# esp8266-adapter.net
KiCad netlist of a schematic drawn in EAGLE
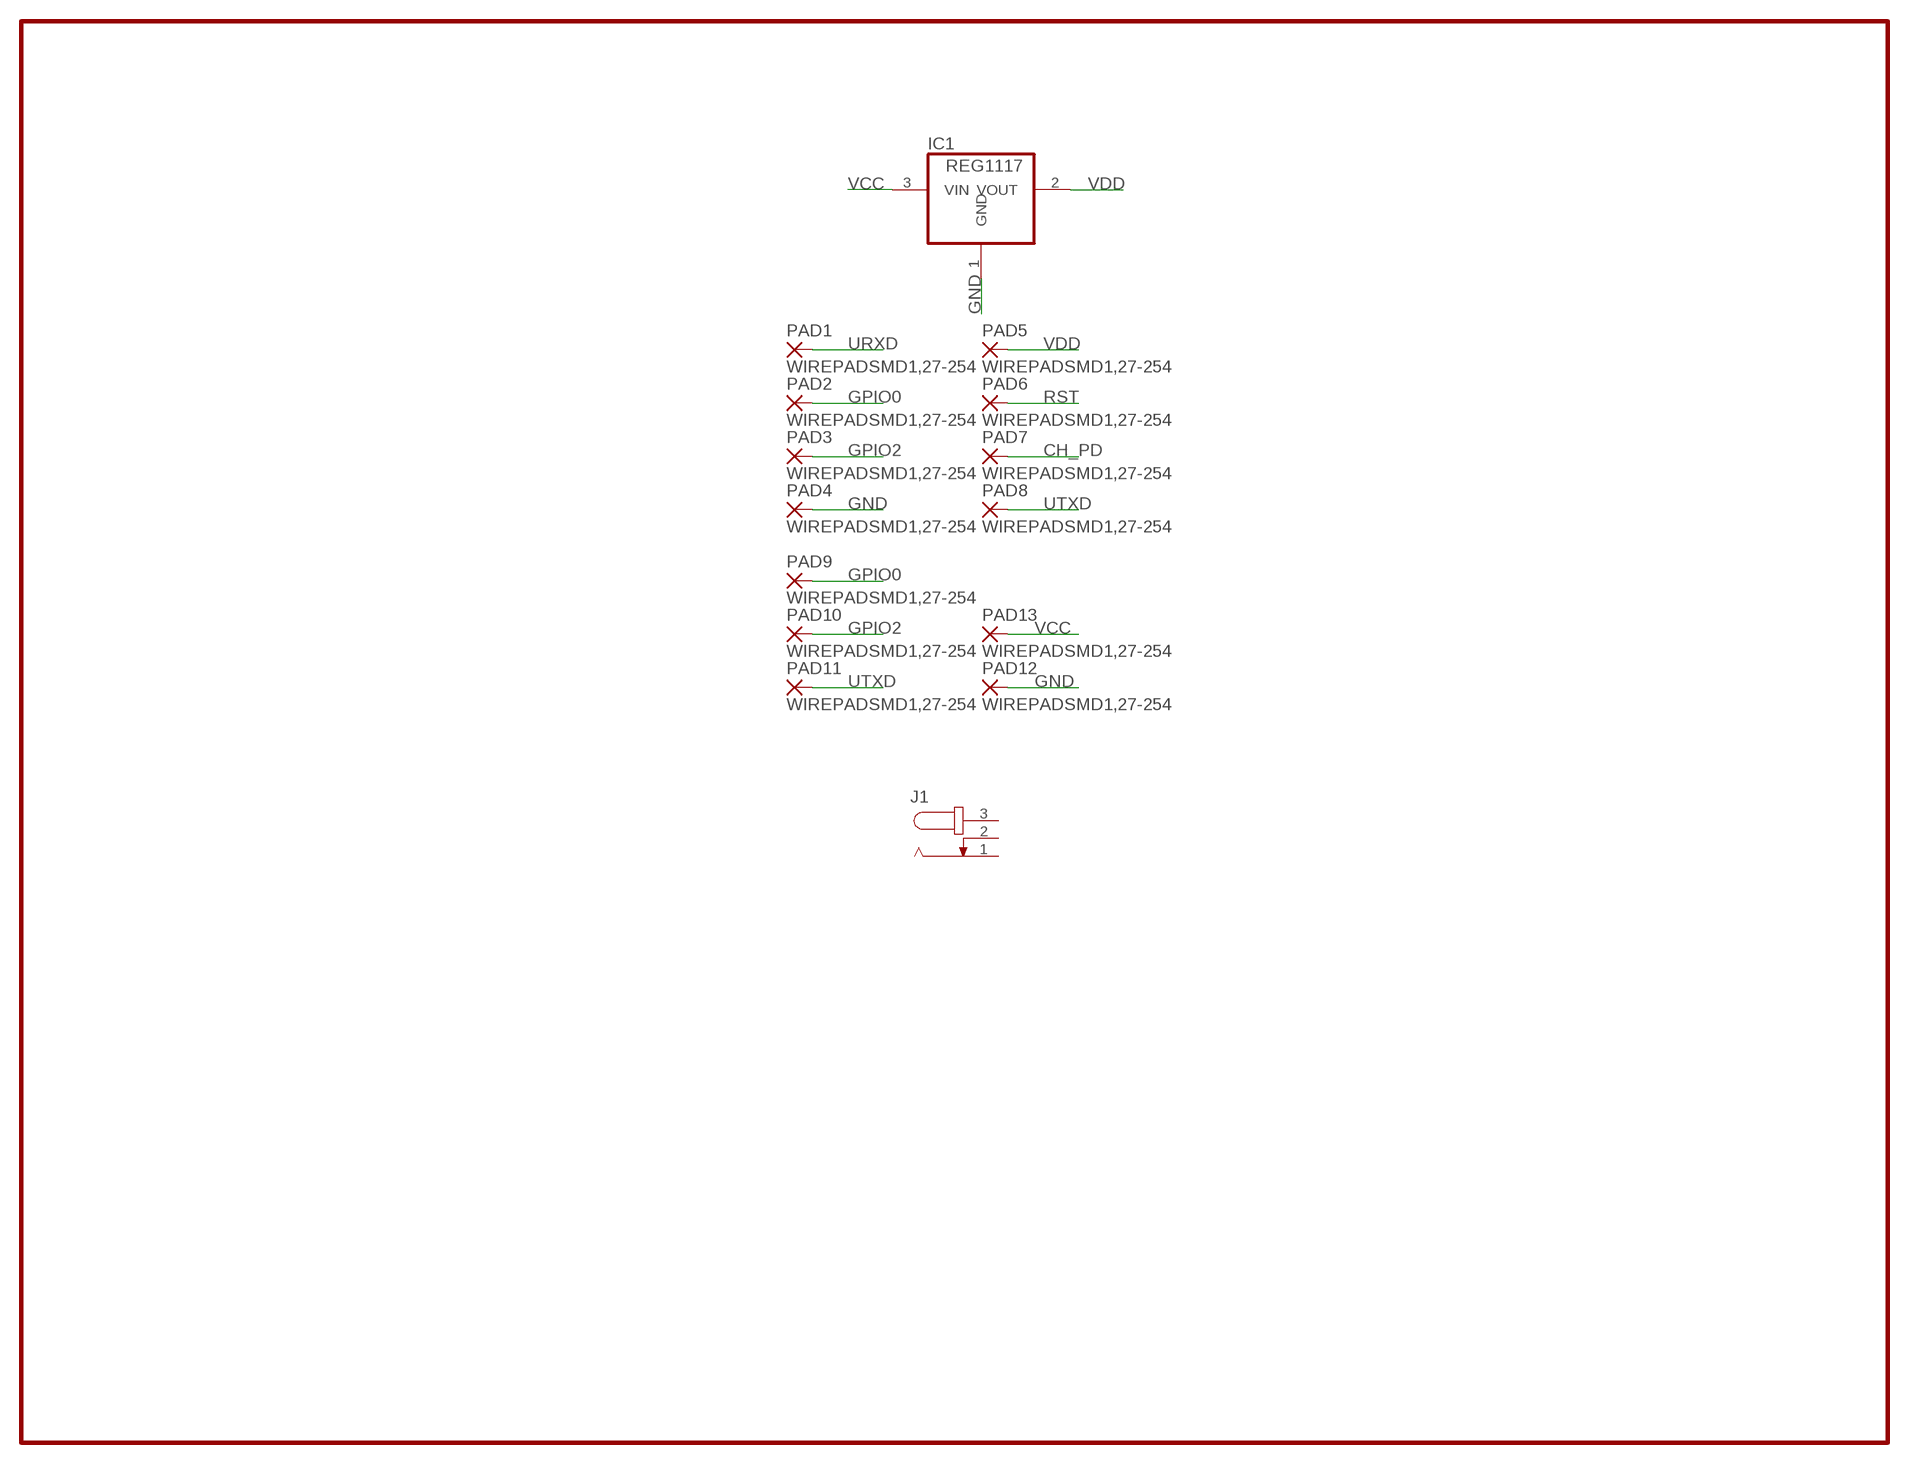
[diagram p0: schematic, sheet 1]

(export (version "E")
  (design (tool "Eeschema 10.0.6"))
  (components
    (comp (ref "IC1")
      (value "REG1117")
      (footprint "eagle-import:SOT223")
      (libsource (lib "eagle-import") (part "REG1117"))
    )
    (comp (ref "J1")
      (value "JACK-PLUG0")
      (footprint "eagle-import:SPC4077")
      (libsource (lib "eagle-import") (part "JACK-PLUG0"))
    )
    (comp (ref "PAD1")
      (value "WIREPADSMD1,27-254")
      (footprint "eagle-import:SMD1,27-2,54")
      (libsource (lib "eagle-import") (part "WIREPADSMD1,27-254"))
    )
    (comp (ref "PAD2")
      (value "WIREPADSMD1,27-254")
      (footprint "eagle-import:SMD1,27-2,54")
      (libsource (lib "eagle-import") (part "WIREPADSMD1,27-254"))
    )
    (comp (ref "PAD3")
      (value "WIREPADSMD1,27-254")
      (footprint "eagle-import:SMD1,27-2,54")
      (libsource (lib "eagle-import") (part "WIREPADSMD1,27-254"))
    )
    (comp (ref "PAD4")
      (value "WIREPADSMD1,27-254")
      (footprint "eagle-import:SMD1,27-2,54")
      (libsource (lib "eagle-import") (part "WIREPADSMD1,27-254"))
    )
    (comp (ref "PAD5")
      (value "WIREPADSMD1,27-254")
      (footprint "eagle-import:SMD1,27-2,54")
      (libsource (lib "eagle-import") (part "WIREPADSMD1,27-254"))
    )
    (comp (ref "PAD6")
      (value "WIREPADSMD1,27-254")
      (footprint "eagle-import:SMD1,27-2,54")
      (libsource (lib "eagle-import") (part "WIREPADSMD1,27-254"))
    )
    (comp (ref "PAD7")
      (value "WIREPADSMD1,27-254")
      (footprint "eagle-import:SMD1,27-2,54")
      (libsource (lib "eagle-import") (part "WIREPADSMD1,27-254"))
    )
    (comp (ref "PAD8")
      (value "WIREPADSMD1,27-254")
      (footprint "eagle-import:SMD1,27-2,54")
      (libsource (lib "eagle-import") (part "WIREPADSMD1,27-254"))
    )
    (comp (ref "PAD9")
      (value "WIREPADSMD1,27-254")
      (footprint "eagle-import:SMD1,27-2,54")
      (libsource (lib "eagle-import") (part "WIREPADSMD1,27-254"))
    )
    (comp (ref "PAD10")
      (value "WIREPADSMD1,27-254")
      (footprint "eagle-import:SMD1,27-2,54")
      (libsource (lib "eagle-import") (part "WIREPADSMD1,27-254"))
    )
    (comp (ref "PAD11")
      (value "WIREPADSMD1,27-254")
      (footprint "eagle-import:SMD1,27-2,54")
      (libsource (lib "eagle-import") (part "WIREPADSMD1,27-254"))
    )
    (comp (ref "PAD12")
      (value "WIREPADSMD1,27-254")
      (footprint "eagle-import:SMD1,27-2,54")
      (libsource (lib "eagle-import") (part "WIREPADSMD1,27-254"))
    )
    (comp (ref "PAD13")
      (value "WIREPADSMD1,27-254")
      (footprint "eagle-import:SMD1,27-2,54")
      (libsource (lib "eagle-import") (part "WIREPADSMD1,27-254"))
    )
  )
  (nets
    (net (code "1") (name "/CH_PD") (class "Default")
      (node (ref "PAD7") (pin "1") (pinfunction "P_1") (pintype "passive"))
    )
    (net (code "2") (name "/GND") (class "Default")
      (node (ref "IC1") (pin "1") (pinfunction "GND_1") (pintype "power_in"))
      (node (ref "PAD12") (pin "1") (pinfunction "P_1") (pintype "passive"))
      (node (ref "PAD4") (pin "1") (pinfunction "P_1") (pintype "passive"))
    )
    (net (code "3") (name "/GPIO0") (class "Default")
      (node (ref "PAD2") (pin "1") (pinfunction "P_1") (pintype "passive"))
      (node (ref "PAD9") (pin "1") (pinfunction "P_1") (pintype "passive"))
    )
    (net (code "4") (name "/GPIO2") (class "Default")
      (node (ref "PAD10") (pin "1") (pinfunction "P_1") (pintype "passive"))
      (node (ref "PAD3") (pin "1") (pinfunction "P_1") (pintype "passive"))
    )
    (net (code "5") (name "/RST") (class "Default")
      (node (ref "PAD6") (pin "1") (pinfunction "P_1") (pintype "passive"))
    )
    (net (code "6") (name "/URXD") (class "Default")
      (node (ref "PAD1") (pin "1") (pinfunction "P_1") (pintype "passive"))
    )
    (net (code "7") (name "/UTXD") (class "Default")
      (node (ref "PAD11") (pin "1") (pinfunction "P_1") (pintype "passive"))
      (node (ref "PAD8") (pin "1") (pinfunction "P_1") (pintype "passive"))
    )
    (net (code "8") (name "/VCC") (class "Default")
      (node (ref "IC1") (pin "3") (pinfunction "VIN_3") (pintype "input"))
      (node (ref "PAD13") (pin "1") (pinfunction "P_1") (pintype "passive"))
    )
    (net (code "9") (name "/VDD") (class "Default")
      (node (ref "IC1") (pin "2") (pinfunction "VOUT_2") (pintype "output"))
      (node (ref "PAD5") (pin "1") (pinfunction "P_1") (pintype "passive"))
    )
    (net (code "10") (name "unconnected-(J1-Pad1)") (class "Default")
      (node (ref "J1") (pin "1") (pinfunction "1_1") (pintype "passive"))
    )
    (net (code "11") (name "unconnected-(J1-Pad2)") (class "Default")
      (node (ref "J1") (pin "2") (pinfunction "2_2") (pintype "passive"))
    )
    (net (code "12") (name "unconnected-(J1-Pad3)") (class "Default")
      (node (ref "J1") (pin "3") (pinfunction "3_3") (pintype "passive"))
    )
  )
)
